# HackHarder.net
KiCad netlist of a schematic drawn in EAGLE
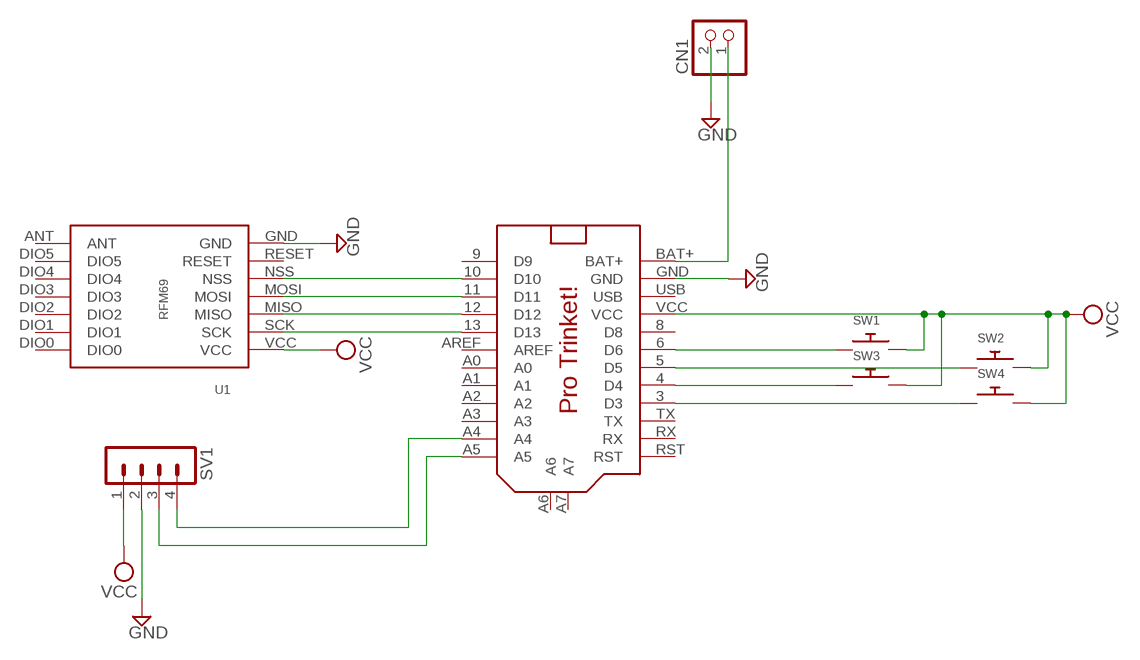
[diagram p0: schematic, sheet 1]

(export (version "E")
  (design (tool "Eeschema 10.0.6"))
  (components
    (comp (ref "CN1")
      (value "JST_2PIN-SMT-RA")
      (footprint "eagle-import:JST-PH-2-SMT-RA")
      (libsource (lib "eagle-import") (part "JST_2PIN-SMT-RA"))
    )
    (comp (ref "MCU1")
      (value "PRO_TRINKET")
      (footprint "eagle-import:PROTRINKET")
      (libsource (lib "eagle-import") (part "PRO_TRINKET"))
    )
    (comp (ref "SV1")
      (value "MA04-1")
      (footprint "eagle-import:MA04-1")
      (libsource (lib "eagle-import") (part "MA04-1"))
    )
    (comp (ref "SW1")
      (value "SWITCH_PUSHBUTTONEVQ-PE")
      (footprint "eagle-import:TACT_PANA-EVQ")
      (libsource (lib "eagle-import") (part "SWITCH_PUSHBUTTONEVQ-PE"))
    )
    (comp (ref "SW2")
      (value "SWITCH_PUSHBUTTONEVQ-PE")
      (footprint "eagle-import:TACT_PANA-EVQ")
      (libsource (lib "eagle-import") (part "SWITCH_PUSHBUTTONEVQ-PE"))
    )
    (comp (ref "SW3")
      (value "SWITCH_PUSHBUTTONEVQ-PE")
      (footprint "eagle-import:TACT_PANA-EVQ")
      (libsource (lib "eagle-import") (part "SWITCH_PUSHBUTTONEVQ-PE"))
    )
    (comp (ref "SW4")
      (value "SWITCH_PUSHBUTTONEVQ-PE")
      (footprint "eagle-import:TACT_PANA-EVQ")
      (libsource (lib "eagle-import") (part "SWITCH_PUSHBUTTONEVQ-PE"))
    )
    (comp (ref "U1")
      (value "RFM69HW")
      (footprint "eagle-import:RFM69_PADS")
      (libsource (lib "eagle-import") (part "RFM69HW"))
    )
  )
  (nets
    (net (code "1") (name "/USB") (class "Default")
      (node (ref "MCU1") (pin "USB") (pinfunction "USB_USB") (pintype "power_in"))
    )
    (net (code "2") (name "GND") (class "Default")
      (node (ref "CN1") (pin "2") (pinfunction "1_2") (pintype "passive"))
      (node (ref "MCU1") (pin "GND") (pinfunction "GND_GND") (pintype "power_in"))
      (node (ref "SV1") (pin "2") (pinfunction "2_2") (pintype "passive"))
      (node (ref "U1") (pin "GND") (pinfunction "GND_GND") (pintype "bidirectional"))
    )
    (net (code "3") (name "Net-(CN1-2)") (class "Default")
      (node (ref "CN1") (pin "1") (pinfunction "2_1") (pintype "passive"))
      (node (ref "MCU1") (pin "BAT+") (pinfunction "BAT+_BAT+") (pintype "power_in"))
    )
    (net (code "4") (name "Net-(MCU1-D3)") (class "Default")
      (node (ref "MCU1") (pin "3") (pinfunction "D3_3") (pintype "bidirectional"))
      (node (ref "SW4") (pin "P$1") (pinfunction "P$1_P$1") (pintype "passive"))
    )
    (net (code "5") (name "Net-(MCU1-D4)") (class "Default")
      (node (ref "MCU1") (pin "4") (pinfunction "D4_4") (pintype "bidirectional"))
      (node (ref "SW3") (pin "P$1") (pinfunction "P$1_P$1") (pintype "passive"))
    )
    (net (code "6") (name "Net-(MCU1-D5)") (class "Default")
      (node (ref "MCU1") (pin "5") (pinfunction "D5_5") (pintype "bidirectional"))
      (node (ref "SW2") (pin "P$1") (pinfunction "P$1_P$1") (pintype "passive"))
    )
    (net (code "7") (name "Net-(MCU1-D6)") (class "Default")
      (node (ref "MCU1") (pin "6") (pinfunction "D6_6") (pintype "bidirectional"))
      (node (ref "SW1") (pin "P$1") (pinfunction "P$1_P$1") (pintype "passive"))
    )
    (net (code "8") (name "Net-(MCU1-D10)") (class "Default")
      (node (ref "MCU1") (pin "10") (pinfunction "D10_10") (pintype "bidirectional"))
      (node (ref "U1") (pin "NSS") (pinfunction "NSS_NSS") (pintype "bidirectional"))
    )
    (net (code "9") (name "Net-(MCU1-D11)") (class "Default")
      (node (ref "MCU1") (pin "11") (pinfunction "D11_11") (pintype "bidirectional"))
      (node (ref "U1") (pin "MOSI") (pinfunction "MOSI_MOSI") (pintype "bidirectional"))
    )
    (net (code "10") (name "Net-(MCU1-D12)") (class "Default")
      (node (ref "MCU1") (pin "12") (pinfunction "D12_12") (pintype "bidirectional"))
      (node (ref "U1") (pin "MISO") (pinfunction "MISO_MISO") (pintype "bidirectional"))
    )
    (net (code "11") (name "Net-(MCU1-D13)") (class "Default")
      (node (ref "MCU1") (pin "13") (pinfunction "D13_13") (pintype "bidirectional"))
      (node (ref "U1") (pin "SCK") (pinfunction "SCK_SCK") (pintype "bidirectional"))
    )
    (net (code "12") (name "Net-(MCU1-PadA4)") (class "Default")
      (node (ref "MCU1") (pin "A4") (pinfunction "A4_A4") (pintype "bidirectional"))
      (node (ref "SV1") (pin "4") (pinfunction "4_4") (pintype "passive"))
    )
    (net (code "13") (name "Net-(MCU1-PadA5)") (class "Default")
      (node (ref "MCU1") (pin "A5") (pinfunction "A5_A5") (pintype "bidirectional"))
      (node (ref "SV1") (pin "3") (pinfunction "3_3") (pintype "passive"))
    )
    (net (code "14") (name "VCC") (class "Default")
      (node (ref "MCU1") (pin "VCC") (pinfunction "VCC_VCC") (pintype "power_in"))
      (node (ref "SV1") (pin "1") (pinfunction "1_1") (pintype "passive"))
      (node (ref "SW1") (pin "P$2") (pinfunction "P$2_P$2") (pintype "passive"))
      (node (ref "SW2") (pin "P$2") (pinfunction "P$2_P$2") (pintype "passive"))
      (node (ref "SW3") (pin "P$2") (pinfunction "P$2_P$2") (pintype "passive"))
      (node (ref "SW4") (pin "P$2") (pinfunction "P$2_P$2") (pintype "passive"))
      (node (ref "U1") (pin "VCC") (pinfunction "VCC_VCC") (pintype "bidirectional"))
    )
    (net (code "15") (name "unconnected-(MCU1-D8-Pad8)") (class "Default")
      (node (ref "MCU1") (pin "8") (pinfunction "D8_8") (pintype "bidirectional"))
    )
    (net (code "16") (name "unconnected-(MCU1-D9-Pad9)") (class "Default")
      (node (ref "MCU1") (pin "9") (pinfunction "D9_9") (pintype "bidirectional"))
    )
    (net (code "17") (name "unconnected-(MCU1-PadA0)") (class "Default")
      (node (ref "MCU1") (pin "A0") (pinfunction "A0_A0") (pintype "bidirectional"))
    )
    (net (code "18") (name "unconnected-(MCU1-PadA1)") (class "Default")
      (node (ref "MCU1") (pin "A1") (pinfunction "A1_A1") (pintype "bidirectional"))
    )
    (net (code "19") (name "unconnected-(MCU1-PadA2)") (class "Default")
      (node (ref "MCU1") (pin "A2") (pinfunction "A2_A2") (pintype "bidirectional"))
    )
    (net (code "20") (name "unconnected-(MCU1-PadA3)") (class "Default")
      (node (ref "MCU1") (pin "A3") (pinfunction "A3_A3") (pintype "bidirectional"))
    )
    (net (code "21") (name "unconnected-(MCU1-PadA6)") (class "Default")
      (node (ref "MCU1") (pin "A6") (pinfunction "A6_A6") (pintype "passive"))
    )
    (net (code "22") (name "unconnected-(MCU1-PadA7)") (class "Default")
      (node (ref "MCU1") (pin "A7") (pinfunction "A7_A7") (pintype "passive"))
    )
    (net (code "23") (name "unconnected-(MCU1-PadAREF)") (class "Default")
      (node (ref "MCU1") (pin "AREF") (pinfunction "AREF_AREF") (pintype "passive"))
    )
    (net (code "24") (name "unconnected-(MCU1-PadRST)") (class "Default")
      (node (ref "MCU1") (pin "RST") (pinfunction "RST_RST") (pintype "passive"))
    )
    (net (code "25") (name "unconnected-(MCU1-PadRX)") (class "Default")
      (node (ref "MCU1") (pin "RX") (pinfunction "RX_RX") (pintype "bidirectional"))
    )
    (net (code "26") (name "unconnected-(MCU1-PadTX)") (class "Default")
      (node (ref "MCU1") (pin "TX") (pinfunction "TX_TX") (pintype "bidirectional"))
    )
    (net (code "27") (name "unconnected-(U1-PadANT)") (class "Default")
      (node (ref "U1") (pin "ANT") (pinfunction "ANT_ANT") (pintype "bidirectional"))
    )
    (net (code "28") (name "unconnected-(U1-PadDIO0)") (class "Default")
      (node (ref "U1") (pin "DIO0") (pinfunction "DIO0_DIO0") (pintype "bidirectional"))
    )
    (net (code "29") (name "unconnected-(U1-PadDIO1)") (class "Default")
      (node (ref "U1") (pin "DIO1") (pinfunction "DIO1_DIO1") (pintype "bidirectional"))
    )
    (net (code "30") (name "unconnected-(U1-PadDIO2)") (class "Default")
      (node (ref "U1") (pin "DIO2") (pinfunction "DIO2_DIO2") (pintype "bidirectional"))
    )
    (net (code "31") (name "unconnected-(U1-PadDIO3)") (class "Default")
      (node (ref "U1") (pin "DIO3") (pinfunction "DIO3_DIO3") (pintype "bidirectional"))
    )
    (net (code "32") (name "unconnected-(U1-PadDIO4)") (class "Default")
      (node (ref "U1") (pin "DIO4") (pinfunction "DIO4_DIO4") (pintype "bidirectional"))
    )
    (net (code "33") (name "unconnected-(U1-PadDIO5)") (class "Default")
      (node (ref "U1") (pin "DIO5") (pinfunction "DIO5_DIO5") (pintype "bidirectional"))
    )
    (net (code "34") (name "unconnected-(U1-PadRESET)") (class "Default")
      (node (ref "U1") (pin "RESET") (pinfunction "RESET_RESET") (pintype "bidirectional"))
    )
  )
)
